# et312.net
KiCad netlist of a schematic drawn in EAGLE
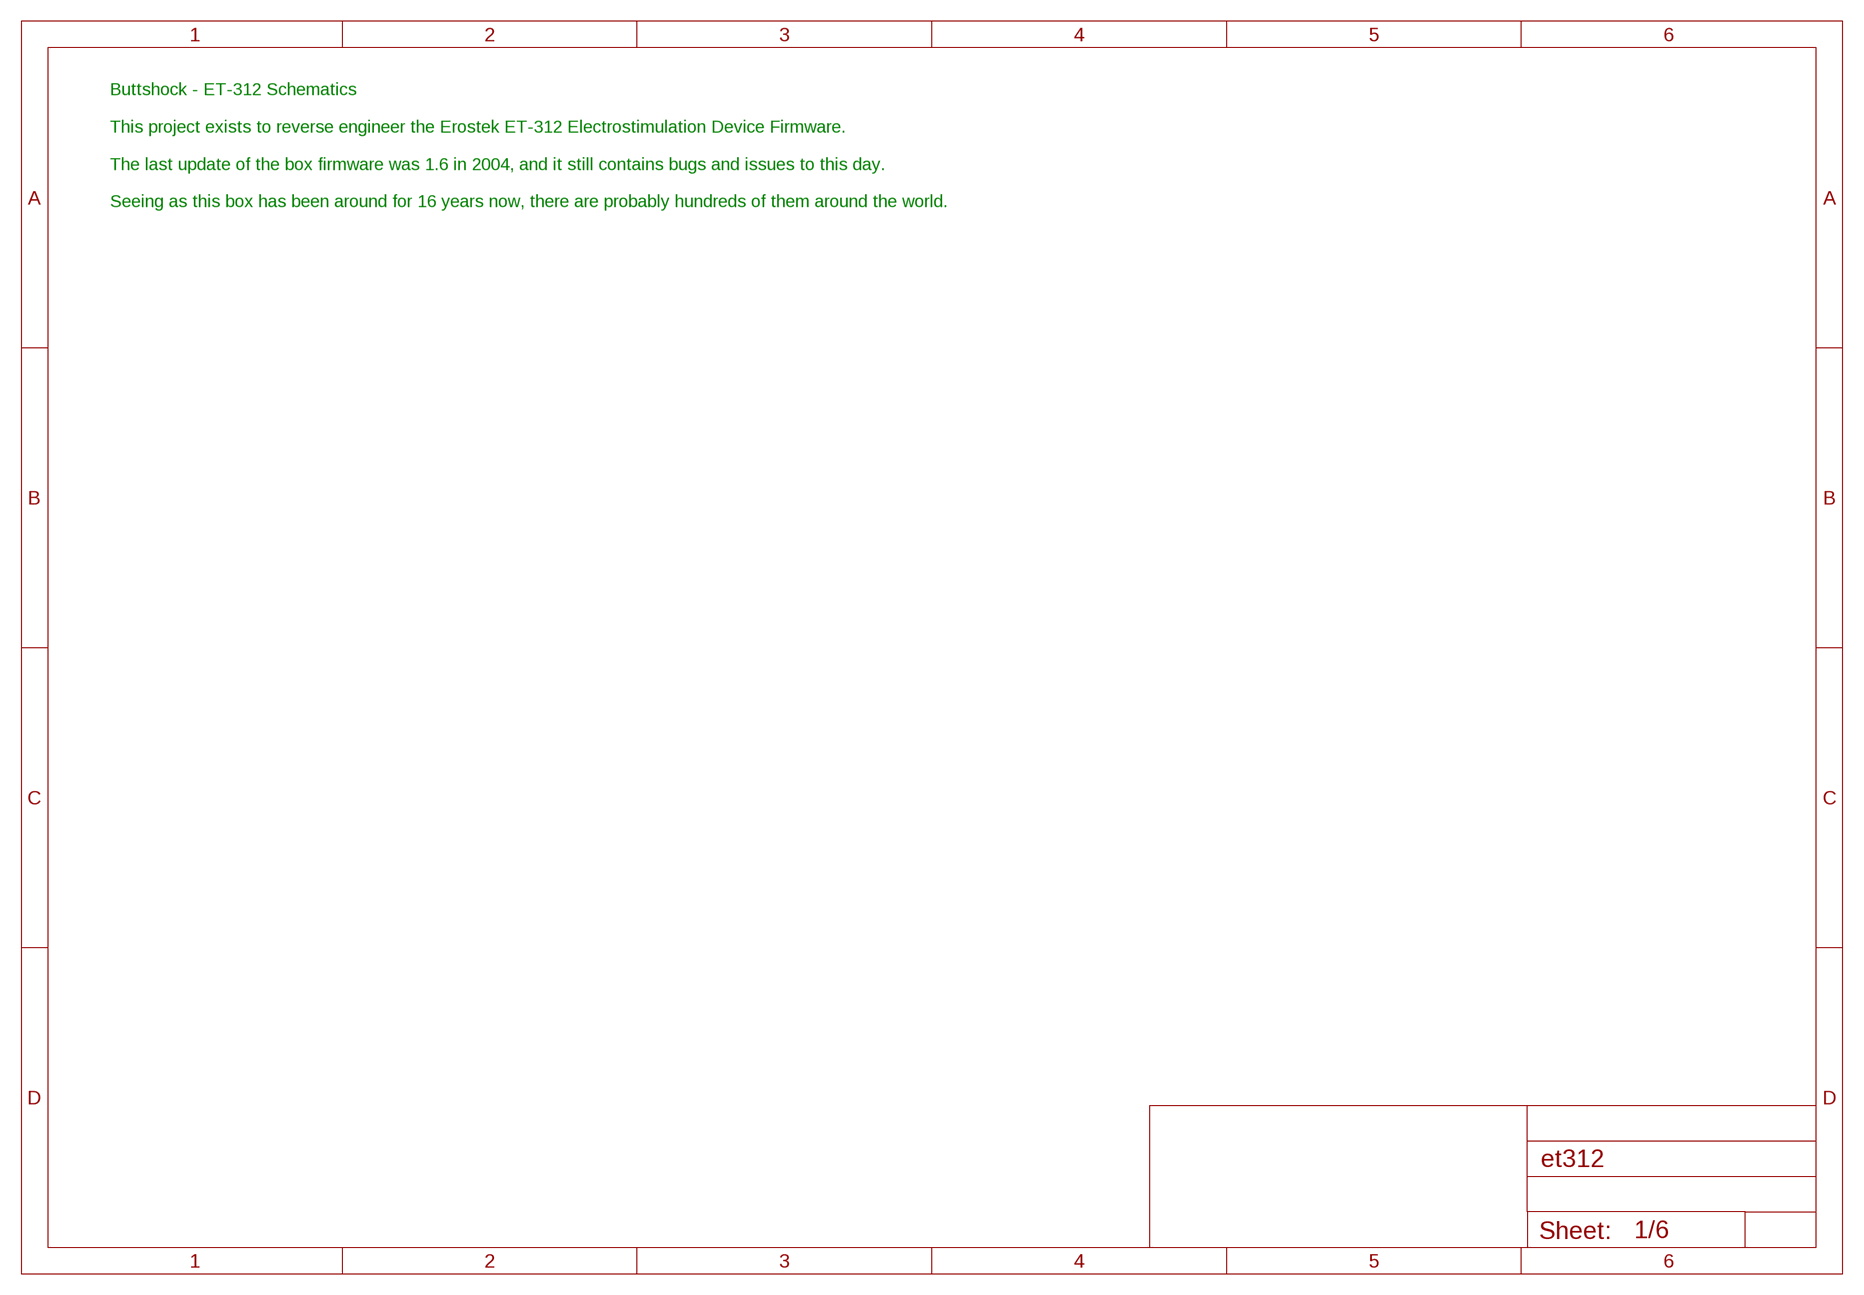
[diagram p0: schematic, sheet 1]
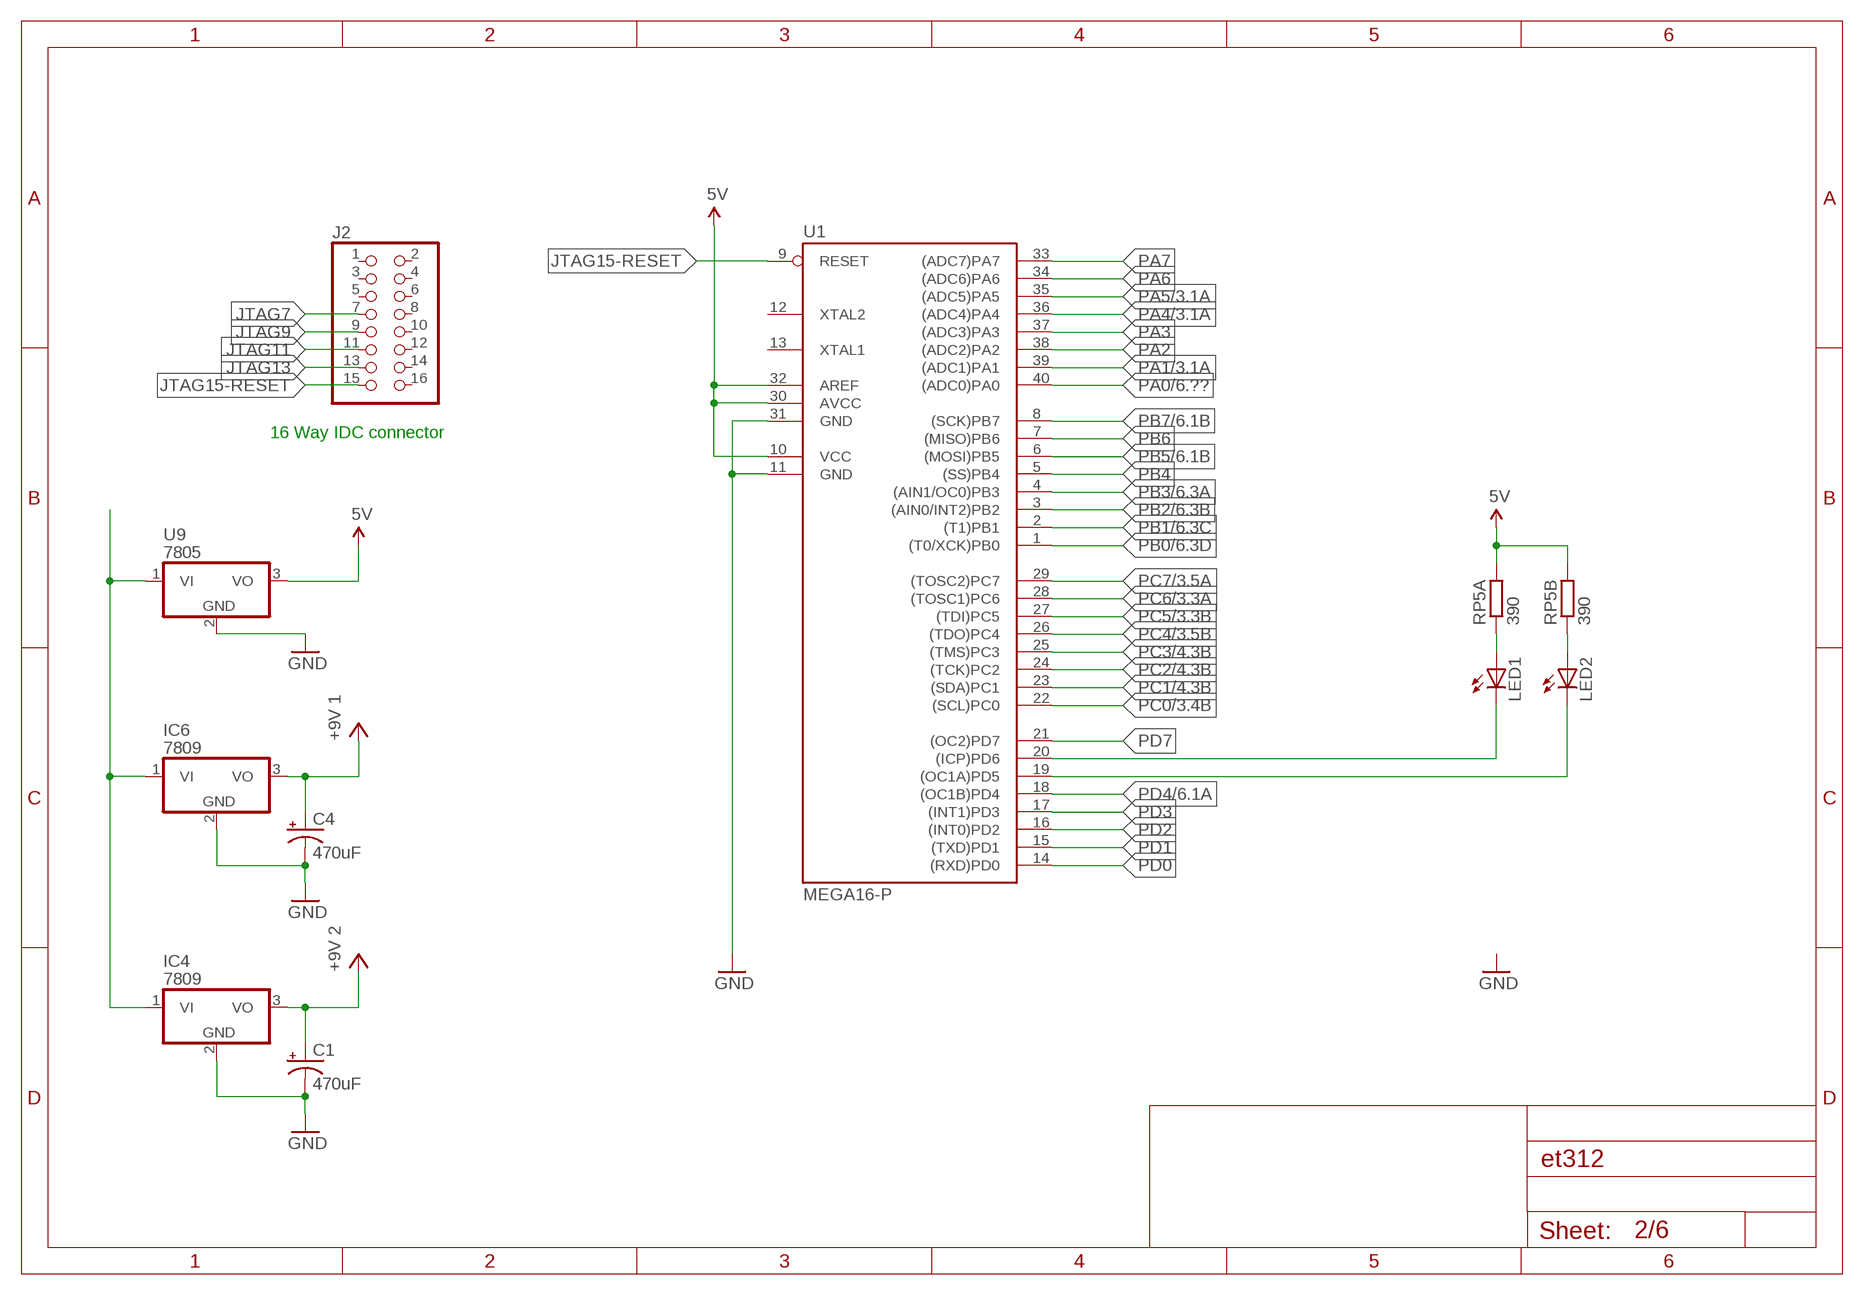
[diagram p1: schematic, sheet 2]
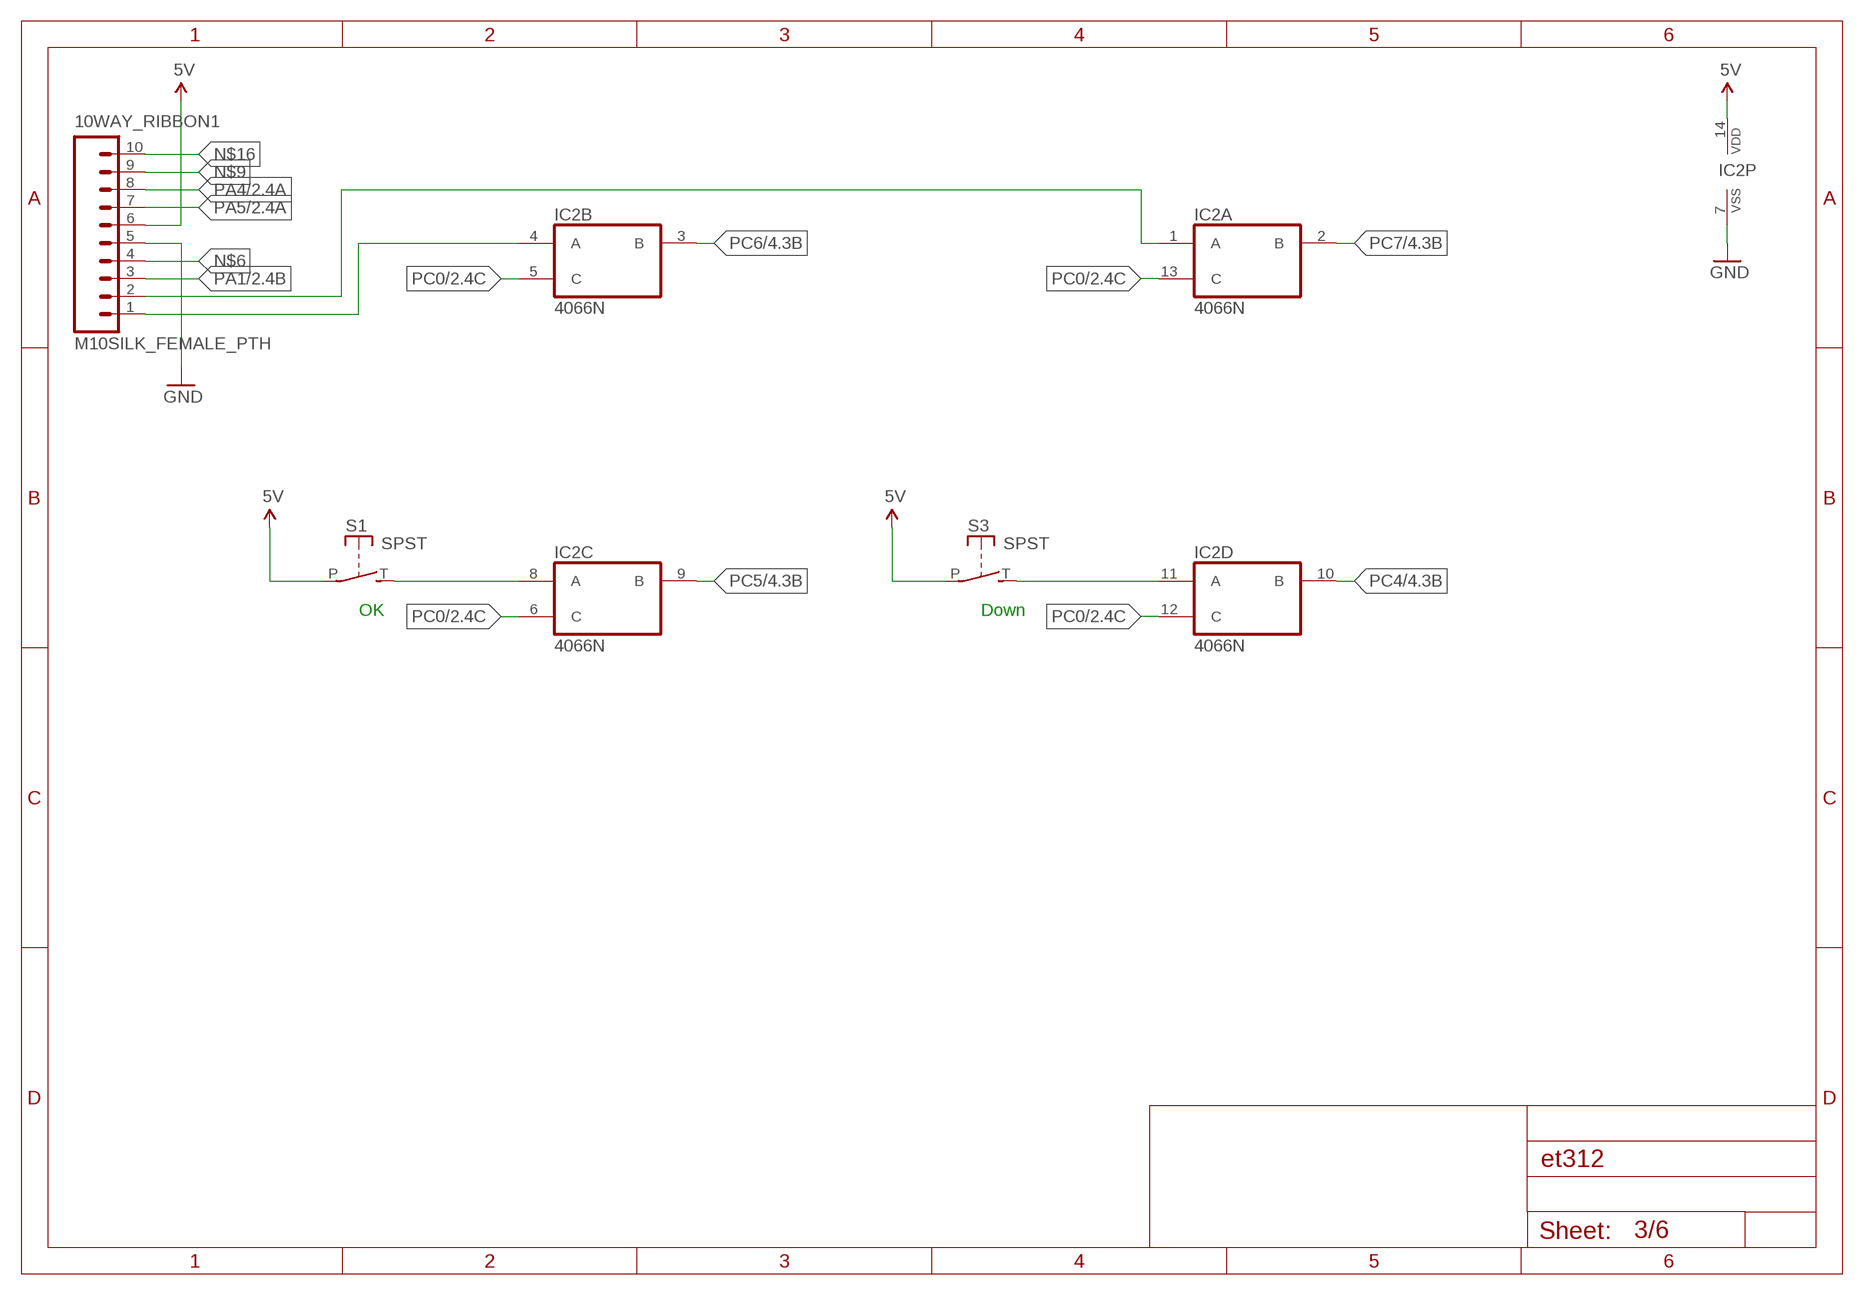
[diagram p2: schematic, sheet 3]
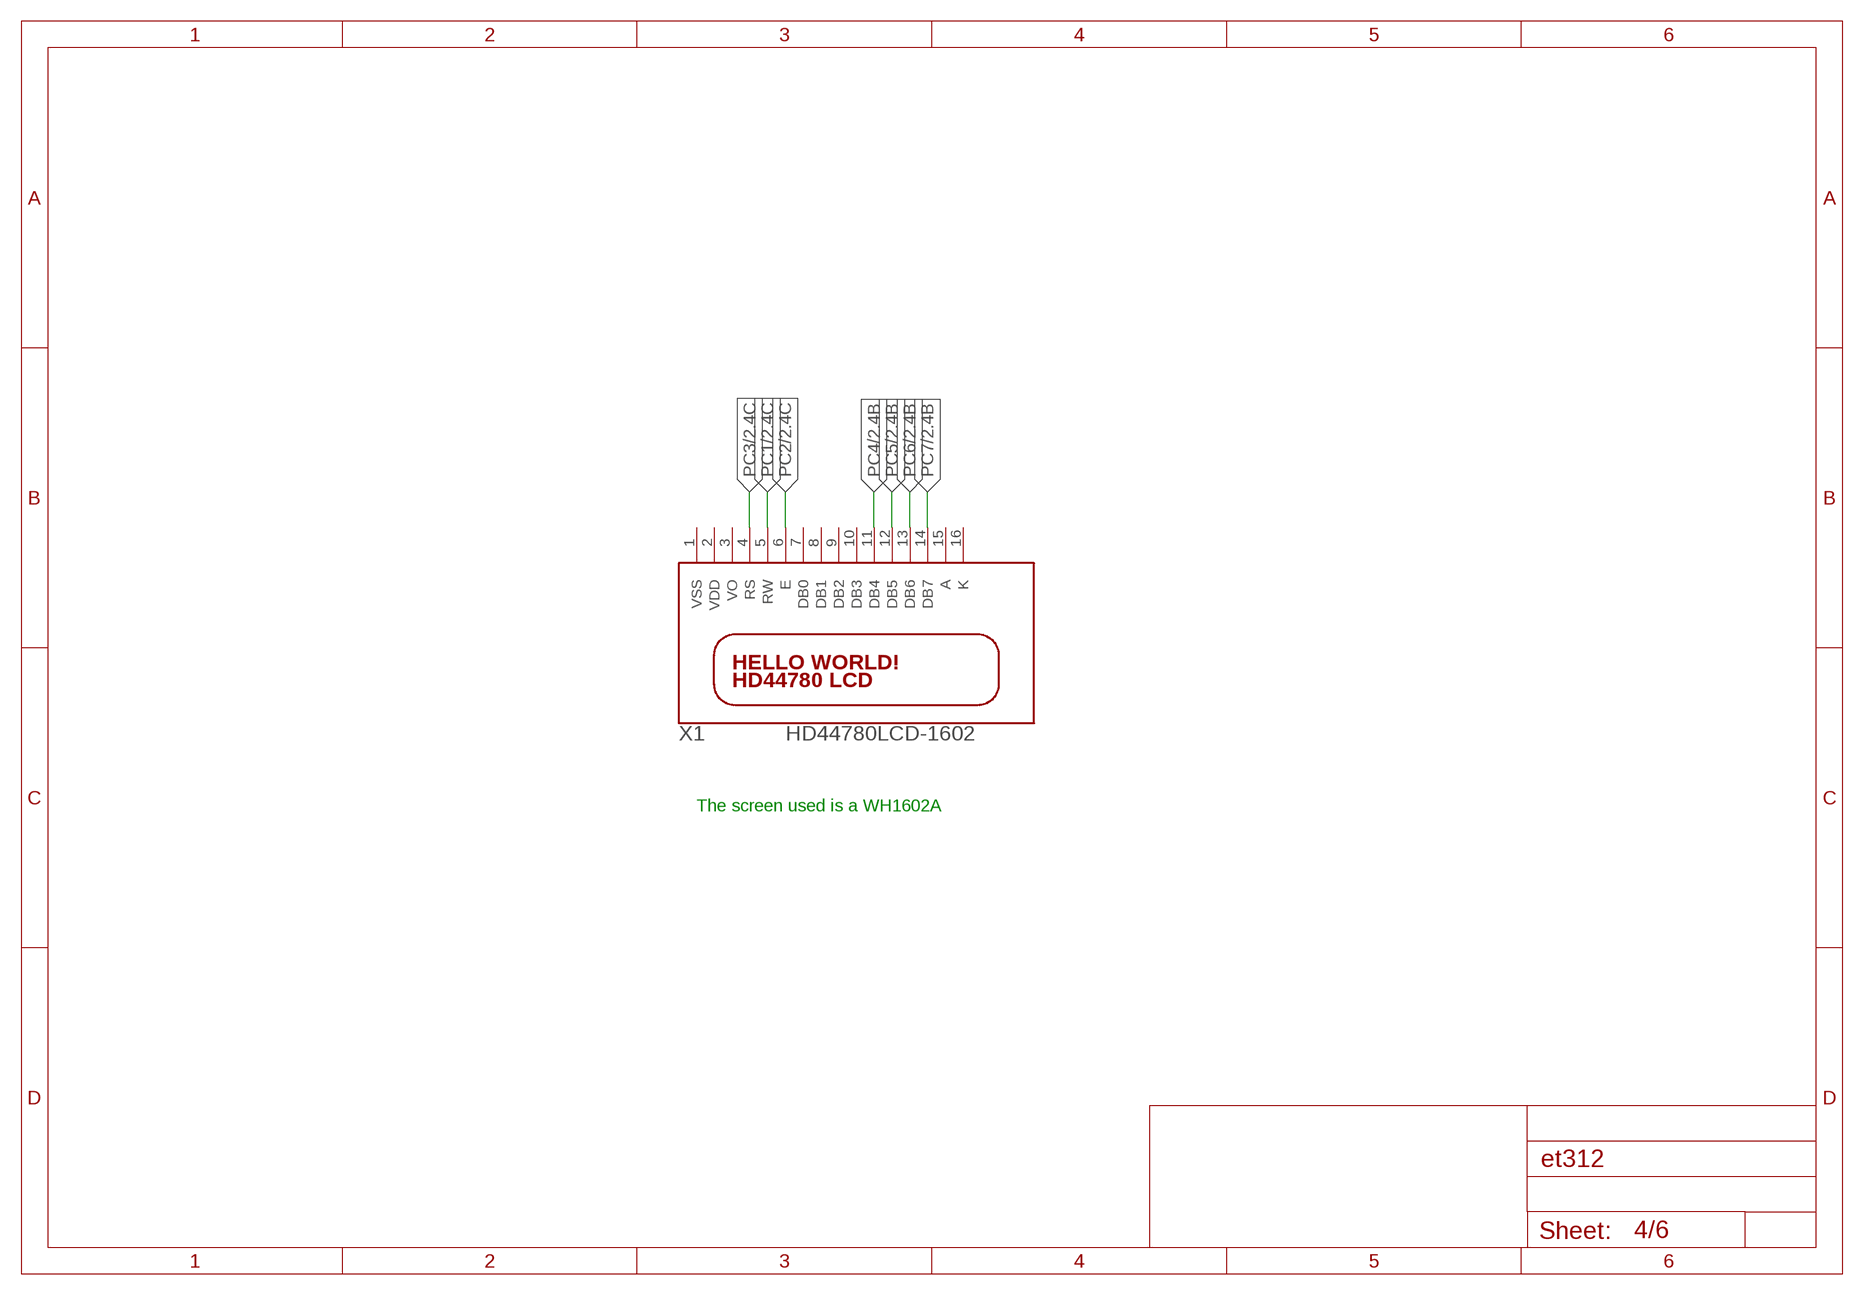
[diagram p3: schematic, sheet 4]
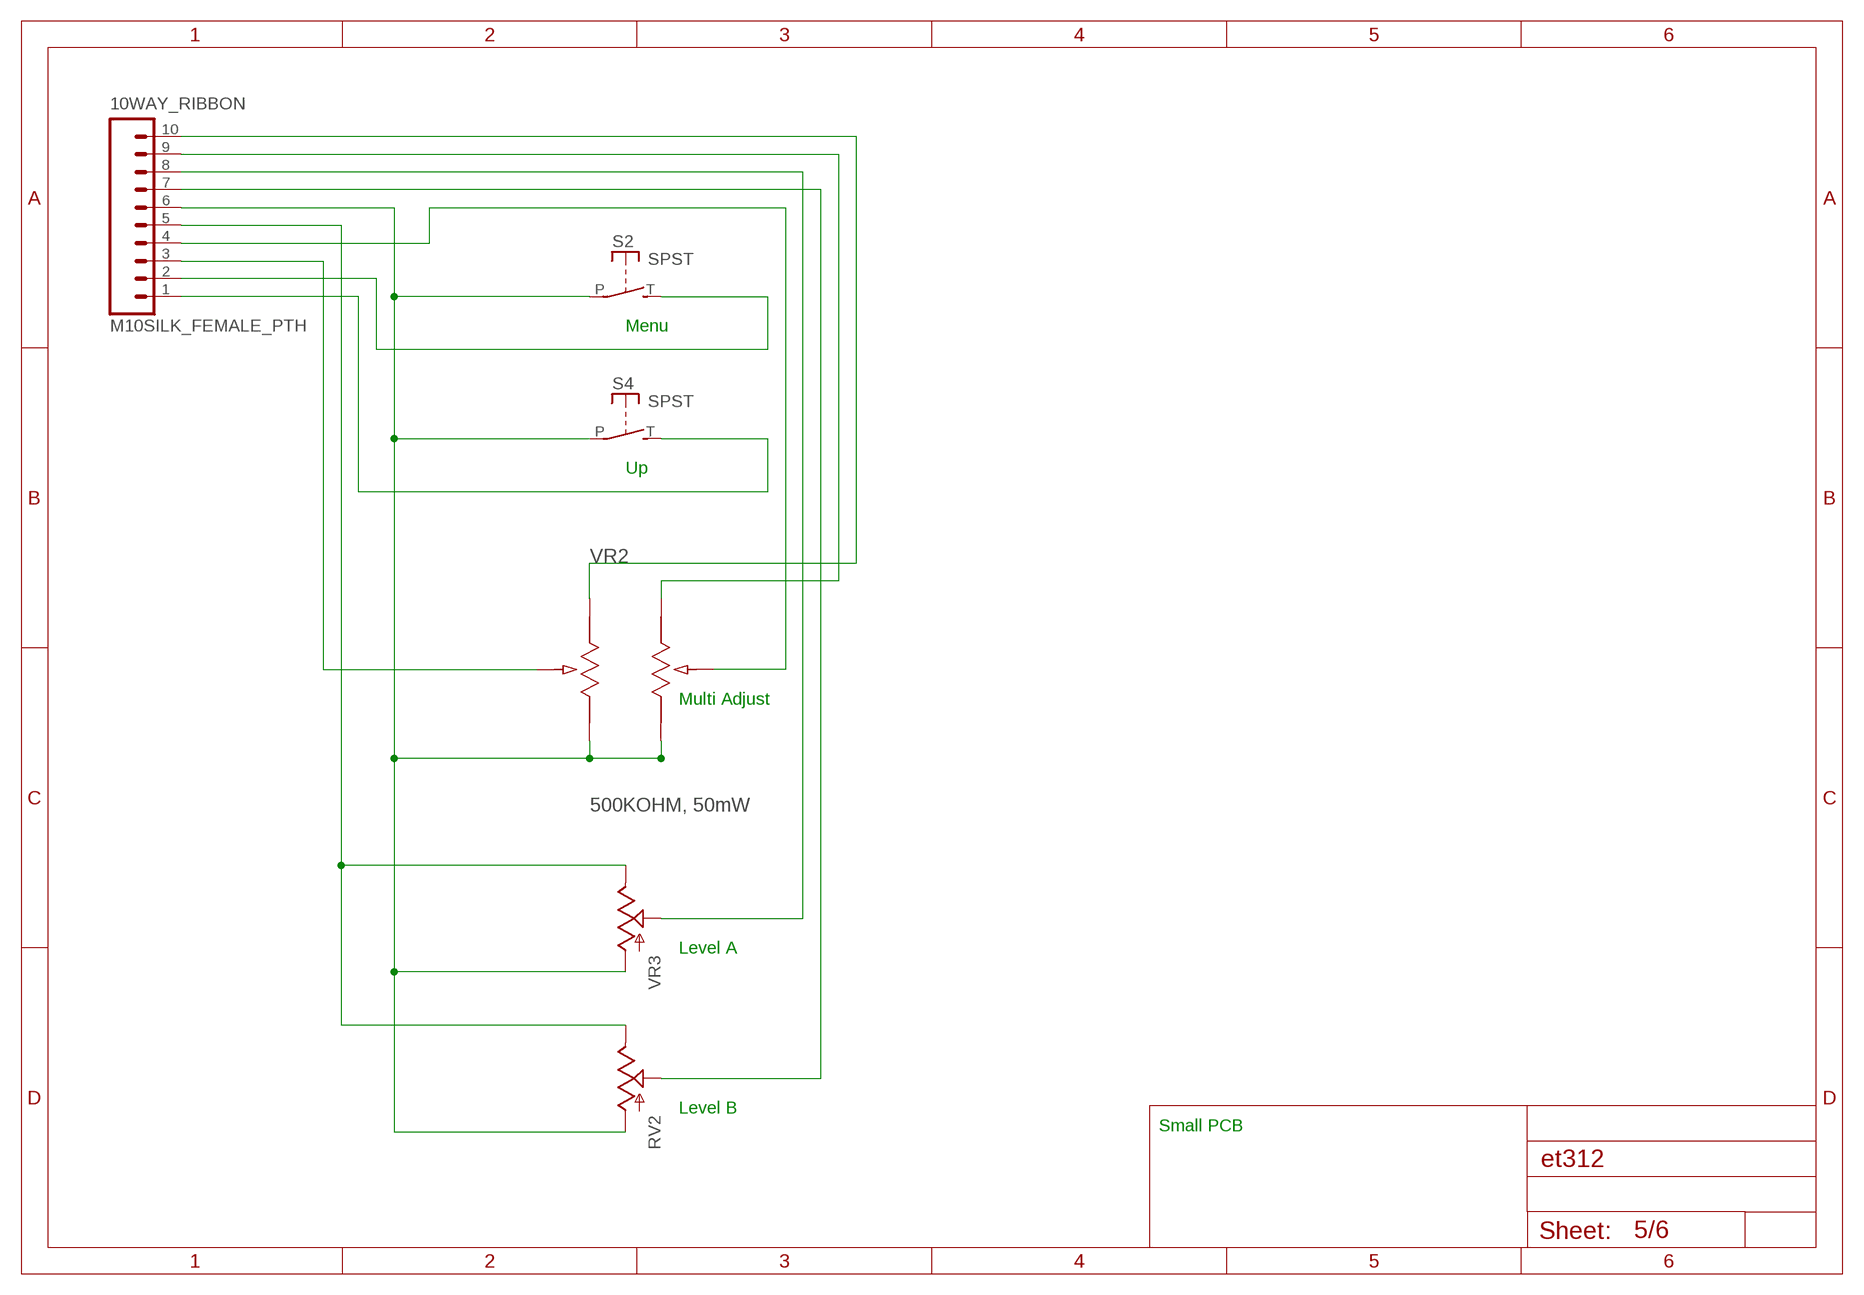
[diagram p4: schematic, sheet 5]
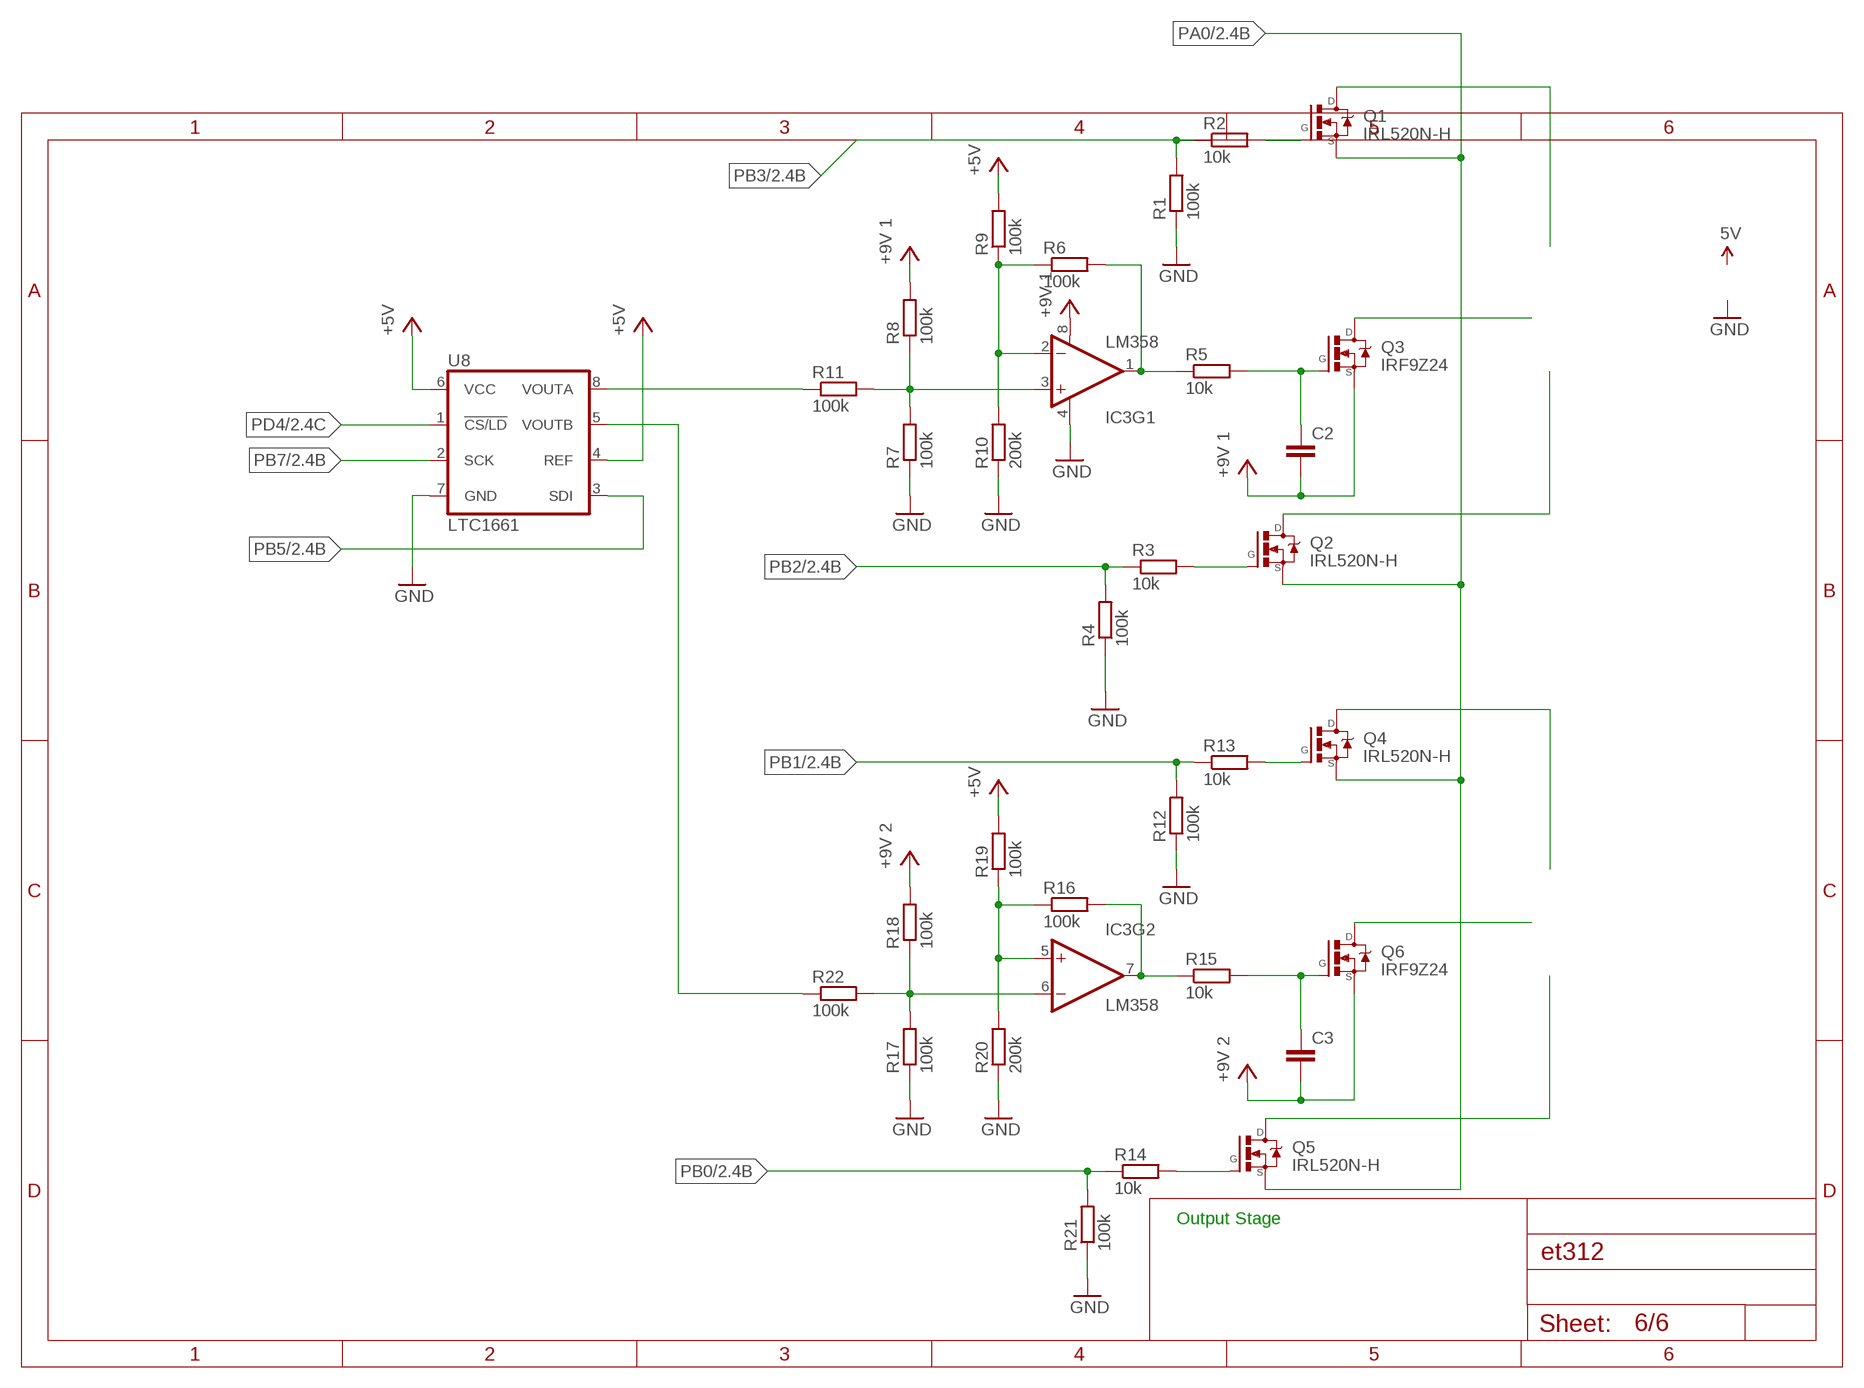
[diagram p5: schematic, sheet 6]

(export (version "E")
  (design (tool "Eeschema 10.0.6"))
  (components
    (comp (ref "10WAY_RIBBON1")
      (value "M10SILK_FEMALE_PTH")
      (footprint "eagle-import:1X10")
      (libsource (lib "eagle-import") (part "M10SILK_FEMALE_PTH"))
    )
    (comp (ref "IC2")
      (value "4066N")
      (footprint "eagle-import:DIL14")
      (libsource (lib "eagle-import") (part "4066N"))
    )
    (comp (ref "S1")
      (value "SPST")
      (footprint "eagle-import:JUDCOSPST")
      (libsource (lib "eagle-import") (part "SPST"))
    )
    (comp (ref "S3")
      (value "SPST")
      (footprint "eagle-import:JUDCOSPST")
      (libsource (lib "eagle-import") (part "SPST"))
    )
    (comp (ref "C2")
      (value "CAPPTH")
      (footprint "eagle-import:CAP-PTH-SMALL")
      (libsource (lib "eagle-import") (part "CAPPTH"))
    )
    (comp (ref "C3")
      (value "CAPPTH")
      (footprint "eagle-import:CAP-PTH-SMALL")
      (libsource (lib "eagle-import") (part "CAPPTH"))
    )
    (comp (ref "IC3")
      (value "LM358")
      (footprint "eagle-import:DIP08")
      (libsource (lib "eagle-import") (part "LM358"))
    )
    (comp (ref "Q1")
      (value "IRL520N-H")
      (footprint "eagle-import:TO220")
      (libsource (lib "eagle-import") (part "IRL530N-H"))
    )
    (comp (ref "Q2")
      (value "IRL520N-H")
      (footprint "eagle-import:TO220")
      (libsource (lib "eagle-import") (part "IRL530N-H"))
    )
    (comp (ref "Q3")
      (value "IRF9Z24")
      (footprint "eagle-import:TO220")
      (libsource (lib "eagle-import") (part "IRL530N-H"))
    )
    (comp (ref "Q4")
      (value "IRL520N-H")
      (footprint "eagle-import:TO220")
      (libsource (lib "eagle-import") (part "IRL530N-H"))
    )
    (comp (ref "Q5")
      (value "IRL520N-H")
      (footprint "eagle-import:TO220")
      (libsource (lib "eagle-import") (part "IRL530N-H"))
    )
    (comp (ref "Q6")
      (value "IRF9Z24")
      (footprint "eagle-import:TO220")
      (libsource (lib "eagle-import") (part "IRL530N-H"))
    )
    (comp (ref "R1")
      (value "100k")
      (footprint "eagle-import:0207_10")
      (libsource (lib "eagle-import") (part "R0207/10"))
    )
    (comp (ref "R2")
      (value "10k")
      (footprint "eagle-import:0207_10")
      (libsource (lib "eagle-import") (part "R0207/10"))
    )
    (comp (ref "R3")
      (value "10k")
      (footprint "eagle-import:0207_10")
      (libsource (lib "eagle-import") (part "R0207/10"))
    )
    (comp (ref "R4")
      (value "100k")
      (footprint "eagle-import:0207_10")
      (libsource (lib "eagle-import") (part "R0207/10"))
    )
    (comp (ref "R5")
      (value "10k")
      (footprint "eagle-import:0207_10")
      (libsource (lib "eagle-import") (part "R0207/10"))
    )
    (comp (ref "R6")
      (value "100k")
      (footprint "eagle-import:0207_10")
      (libsource (lib "eagle-import") (part "R0207/10"))
    )
    (comp (ref "R7")
      (value "100k")
      (footprint "eagle-import:0207_10")
      (libsource (lib "eagle-import") (part "R0207/10"))
    )
    (comp (ref "R8")
      (value "100k")
      (footprint "eagle-import:0207_10")
      (libsource (lib "eagle-import") (part "R0207/10"))
    )
    (comp (ref "R9")
      (value "100k")
      (footprint "eagle-import:0207_10")
      (libsource (lib "eagle-import") (part "R0207/10"))
    )
    (comp (ref "R10")
      (value "200k")
      (footprint "eagle-import:0207_10")
      (libsource (lib "eagle-import") (part "R0207/10"))
    )
    (comp (ref "R11")
      (value "100k")
      (footprint "eagle-import:0207_10")
      (libsource (lib "eagle-import") (part "R0207/10"))
    )
    (comp (ref "R12")
      (value "100k")
      (footprint "eagle-import:0207_10")
      (libsource (lib "eagle-import") (part "R0207/10"))
    )
    (comp (ref "R13")
      (value "10k")
      (footprint "eagle-import:0207_10")
      (libsource (lib "eagle-import") (part "R0207/10"))
    )
    (comp (ref "R14")
      (value "10k")
      (footprint "eagle-import:0207_10")
      (libsource (lib "eagle-import") (part "R0207/10"))
    )
    (comp (ref "R15")
      (value "10k")
      (footprint "eagle-import:0207_10")
      (libsource (lib "eagle-import") (part "R0207/10"))
    )
    (comp (ref "R16")
      (value "100k")
      (footprint "eagle-import:0207_10")
      (libsource (lib "eagle-import") (part "R0207/10"))
    )
    (comp (ref "R17")
      (value "100k")
      (footprint "eagle-import:0207_10")
      (libsource (lib "eagle-import") (part "R0207/10"))
    )
    (comp (ref "R18")
      (value "100k")
      (footprint "eagle-import:0207_10")
      (libsource (lib "eagle-import") (part "R0207/10"))
    )
    (comp (ref "R19")
      (value "100k")
      (footprint "eagle-import:0207_10")
      (libsource (lib "eagle-import") (part "R0207/10"))
    )
    (comp (ref "R20")
      (value "200k")
      (footprint "eagle-import:0207_10")
      (libsource (lib "eagle-import") (part "R0207/10"))
    )
    (comp (ref "R21")
      (value "100k")
      (footprint "eagle-import:0207_10")
      (libsource (lib "eagle-import") (part "R0207/10"))
    )
    (comp (ref "R22")
      (value "100k")
      (footprint "eagle-import:0207_10")
      (libsource (lib "eagle-import") (part "R0207/10"))
    )
    (comp (ref "U8")
      (value "LTC1661")
      (footprint "eagle-import:MSOP8")
      (fields (field (name "MPN") "LTC2602CMS8"))
      (libsource (lib "eagle-import") (part "LTC26MS802C"))
    )
    (comp (ref "X1")
      (value "HD44780LCD-1602")
      (footprint "eagle-import:LCD1602")
      (libsource (lib "eagle-import") (part "HD44780LCD-1602"))
    )
    (comp (ref "10WAY_RIBBON")
      (value "M10SILK_FEMALE_PTH")
      (footprint "eagle-import:1X10")
      (libsource (lib "eagle-import") (part "M10SILK_FEMALE_PTH"))
    )
    (comp (ref "RV2")
      (value "POT")
      (footprint "eagle-import:ALPS_POT")
      (libsource (lib "eagle-import") (part "POT"))
    )
    (comp (ref "S2")
      (value "SPST")
      (footprint "eagle-import:JUDCOSPST")
      (libsource (lib "eagle-import") (part "SPST"))
    )
    (comp (ref "S4")
      (value "SPST")
      (footprint "eagle-import:JUDCOSPST")
      (libsource (lib "eagle-import") (part "SPST"))
    )
    (comp (ref "VR2")
      (value "500KOHM, 50mW")
      (footprint "eagle-import:POT_EVJC20")
      (fields (field (name "MPN") "EVJC20F02A14"))
      (libsource (lib "eagle-import") (part "EVJ-JC2C20F02A14"))
    )
    (comp (ref "VR3")
      (value "POT")
      (footprint "eagle-import:ALPS_POT")
      (libsource (lib "eagle-import") (part "POT"))
    )
    (comp (ref "C1")
      (value "470uF")
      (footprint "eagle-import:CPOL-RADIAL-100UF-25V")
      (libsource (lib "eagle-import") (part "CAP_POLPTH1"))
    )
    (comp (ref "C4")
      (value "470uF")
      (footprint "eagle-import:CPOL-RADIAL-100UF-25V")
      (libsource (lib "eagle-import") (part "CAP_POLPTH1"))
    )
    (comp (ref "IC4")
      (value "7809")
      (footprint "eagle-import:TO220H")
      (libsource (lib "eagle-import") (part "78T05"))
    )
    (comp (ref "IC6")
      (value "7809")
      (footprint "eagle-import:TO220H")
      (libsource (lib "eagle-import") (part "78T05"))
    )
    (comp (ref "J2")
      (value "PINHD-2X8")
      (footprint "eagle-import:2X08")
      (libsource (lib "eagle-import") (part "PINHD-2X8"))
    )
    (comp (ref "LED1")
      (value "LED3MM")
      (footprint "eagle-import:LED3MM")
      (libsource (lib "eagle-import") (part "LED3MM"))
    )
    (comp (ref "LED2")
      (value "LED3MM")
      (footprint "eagle-import:LED3MM")
      (libsource (lib "eagle-import") (part "LED3MM"))
    )
    (comp (ref "RP5A")
      (value "390")
      (footprint "eagle-import:0207_7")
      (libsource (lib "eagle-import") (part "R-EU_0207/7"))
    )
    (comp (ref "RP5B")
      (value "390")
      (footprint "eagle-import:0207_7")
      (libsource (lib "eagle-import") (part "R-EU_0207/7"))
    )
    (comp (ref "U1")
      (value "MEGA16-P")
      (footprint "eagle-import:DIL40")
      (fields (field (name "MPN") "ATMEGA16-16PU"))
      (libsource (lib "eagle-import") (part "MEGA16-P"))
    )
    (comp (ref "U9")
      (value "7805")
      (footprint "eagle-import:TO220H")
      (libsource (lib "eagle-import") (part "78T05"))
    )
  )
  (nets
    (net (code "1") (name "5V") (class "Default")
      (node (ref "10WAY_RIBBON1") (pin "6") (pinfunction "6_6") (pintype "passive"))
      (node (ref "IC2") (pin "14") (pinfunction "VDD_14") (pintype "power_in"))
      (node (ref "RP5A") (pin "2") (pinfunction "2_2") (pintype "passive"))
      (node (ref "RP5B") (pin "2") (pinfunction "2_2") (pintype "passive"))
      (node (ref "S1") (pin "P") (pinfunction "P_P") (pintype "passive"))
      (node (ref "S3") (pin "P") (pinfunction "P_P") (pintype "passive"))
      (node (ref "U1") (pin "10") (pinfunction "VCC_10") (pintype "power_in"))
      (node (ref "U1") (pin "30") (pinfunction "AVCC_30") (pintype "power_in"))
      (node (ref "U1") (pin "32") (pinfunction "AREF_32") (pintype "passive"))
      (node (ref "U9") (pin "3") (pinfunction "VO_3") (pintype "passive"))
    )
    (net (code "2") (name "GND") (class "Default")
      (node (ref "10WAY_RIBBON1") (pin "5") (pinfunction "5_5") (pintype "passive"))
      (node (ref "C1") (pin "2") (pinfunction "-_2") (pintype "passive"))
      (node (ref "C4") (pin "2") (pinfunction "-_2") (pintype "passive"))
      (node (ref "IC2") (pin "7") (pinfunction "VSS_7") (pintype "power_in"))
      (node (ref "IC3") (pin "4") (pinfunction "V-_4") (pintype "power_in"))
      (node (ref "IC4") (pin "2") (pinfunction "GND_2") (pintype "passive"))
      (node (ref "IC6") (pin "2") (pinfunction "GND_2") (pintype "passive"))
      (node (ref "R1") (pin "1") (pinfunction "1_1") (pintype "passive"))
      (node (ref "R10") (pin "1") (pinfunction "1_1") (pintype "passive"))
      (node (ref "R12") (pin "1") (pinfunction "1_1") (pintype "passive"))
      (node (ref "R17") (pin "1") (pinfunction "1_1") (pintype "passive"))
      (node (ref "R20") (pin "1") (pinfunction "1_1") (pintype "passive"))
      (node (ref "R21") (pin "1") (pinfunction "1_1") (pintype "passive"))
      (node (ref "R4") (pin "1") (pinfunction "1_1") (pintype "passive"))
      (node (ref "R7") (pin "1") (pinfunction "1_1") (pintype "passive"))
      (node (ref "U1") (pin "11") (pinfunction "GND_11") (pintype "power_in"))
      (node (ref "U1") (pin "31") (pinfunction "GND_31") (pintype "power_in"))
      (node (ref "U8") (pin "7") (pinfunction "GND_7") (pintype "power_in"))
      (node (ref "U9") (pin "2") (pinfunction "GND_2") (pintype "passive"))
    )
    (net (code "3") (name "JTAG7") (class "Default")
      (node (ref "J2") (pin "7") (pinfunction "7_7") (pintype "passive"))
    )
    (net (code "4") (name "JTAG9") (class "Default")
      (node (ref "J2") (pin "9") (pinfunction "9_9") (pintype "passive"))
    )
    (net (code "5") (name "JTAG11") (class "Default")
      (node (ref "J2") (pin "11") (pinfunction "11_11") (pintype "passive"))
    )
    (net (code "6") (name "JTAG13") (class "Default")
      (node (ref "J2") (pin "13") (pinfunction "13_13") (pintype "passive"))
    )
    (net (code "7") (name "JTAG15-RESET") (class "Default")
      (node (ref "J2") (pin "15") (pinfunction "15_15") (pintype "passive"))
      (node (ref "U1") (pin "9") (pinfunction "RESET_9") (pintype "input"))
    )
    (net (code "8") (name "N$6") (class "Default")
      (node (ref "10WAY_RIBBON1") (pin "4") (pinfunction "4_4") (pintype "passive"))
    )
    (net (code "9") (name "N$9") (class "Default")
      (node (ref "10WAY_RIBBON1") (pin "9") (pinfunction "9_9") (pintype "passive"))
    )
    (net (code "10") (name "N$16") (class "Default")
      (node (ref "10WAY_RIBBON1") (pin "10") (pinfunction "10_10") (pintype "passive"))
    )
    (net (code "11") (name "Net-(10WAY_RIBBON-Pad3)") (class "Default")
      (node (ref "10WAY_RIBBON") (pin "3") (pinfunction "3_3") (pintype "passive"))
      (node (ref "VR2") (pin "2") (pinfunction "2_2") (pintype "passive"))
    )
    (net (code "12") (name "Net-(10WAY_RIBBON-Pad4)") (class "Default")
      (node (ref "10WAY_RIBBON") (pin "4") (pinfunction "4_4") (pintype "passive"))
      (node (ref "VR2") (pin "2'") (pinfunction "2'_2'") (pintype "passive"))
    )
    (net (code "13") (name "Net-(10WAY_RIBBON-Pad9)") (class "Default")
      (node (ref "10WAY_RIBBON") (pin "9") (pinfunction "9_9") (pintype "passive"))
      (node (ref "VR2") (pin "3'") (pinfunction "3'_3'") (pintype "passive"))
    )
    (net (code "14") (name "Net-(10WAY_RIBBON-Pad10)") (class "Default")
      (node (ref "10WAY_RIBBON") (pin "10") (pinfunction "10_10") (pintype "passive"))
      (node (ref "VR2") (pin "3") (pinfunction "3_3") (pintype "passive"))
    )
    (net (code "15") (name "Net-(IC2A-A)") (class "Default")
      (node (ref "10WAY_RIBBON1") (pin "2") (pinfunction "2_2") (pintype "passive"))
      (node (ref "IC2") (pin "1") (pinfunction "A_1") (pintype "tri_state"))
    )
    (net (code "16") (name "Net-(IC2B-A)") (class "Default")
      (node (ref "10WAY_RIBBON1") (pin "1") (pinfunction "1_1") (pintype "passive"))
      (node (ref "IC2") (pin "4") (pinfunction "A_4") (pintype "tri_state"))
    )
    (net (code "17") (name "Net-(IC2C-A)") (class "Default")
      (node (ref "IC2") (pin "8") (pinfunction "A_8") (pintype "tri_state"))
      (node (ref "S1") (pin "T") (pinfunction "S_T") (pintype "passive"))
    )
    (net (code "18") (name "Net-(IC2D-A)") (class "Default")
      (node (ref "IC2") (pin "11") (pinfunction "A_11") (pintype "tri_state"))
      (node (ref "S3") (pin "T") (pinfunction "S_T") (pintype "passive"))
    )
    (net (code "19") (name "Net-(IC3A-+IN)") (class "Default")
      (node (ref "IC3") (pin "3") (pinfunction "+IN_3") (pintype "input"))
      (node (ref "R11") (pin "2") (pinfunction "2_2") (pintype "passive"))
      (node (ref "R7") (pin "2") (pinfunction "2_2") (pintype "passive"))
      (node (ref "R8") (pin "1") (pinfunction "1_1") (pintype "passive"))
    )
    (net (code "20") (name "Net-(IC3A--IN)") (class "Default")
      (node (ref "IC3") (pin "2") (pinfunction "-IN_2") (pintype "input"))
      (node (ref "R10") (pin "2") (pinfunction "2_2") (pintype "passive"))
      (node (ref "R6") (pin "1") (pinfunction "1_1") (pintype "passive"))
      (node (ref "R9") (pin "1") (pinfunction "1_1") (pintype "passive"))
    )
    (net (code "21") (name "Net-(IC3A-OUT)") (class "Default")
      (node (ref "IC3") (pin "1") (pinfunction "OUT_1") (pintype "output"))
      (node (ref "R5") (pin "1") (pinfunction "1_1") (pintype "passive"))
      (node (ref "R6") (pin "2") (pinfunction "2_2") (pintype "passive"))
    )
    (net (code "22") (name "Net-(IC3B-+IN)") (class "Default")
      (node (ref "IC3") (pin "5") (pinfunction "+IN_5") (pintype "input"))
      (node (ref "R16") (pin "1") (pinfunction "1_1") (pintype "passive"))
      (node (ref "R19") (pin "1") (pinfunction "1_1") (pintype "passive"))
      (node (ref "R20") (pin "2") (pinfunction "2_2") (pintype "passive"))
    )
    (net (code "23") (name "Net-(IC3B--IN)") (class "Default")
      (node (ref "IC3") (pin "6") (pinfunction "-IN_6") (pintype "input"))
      (node (ref "R17") (pin "2") (pinfunction "2_2") (pintype "passive"))
      (node (ref "R18") (pin "1") (pinfunction "1_1") (pintype "passive"))
      (node (ref "R22") (pin "2") (pinfunction "2_2") (pintype "passive"))
    )
    (net (code "24") (name "Net-(IC3B-OUT)") (class "Default")
      (node (ref "IC3") (pin "7") (pinfunction "OUT_7") (pintype "output"))
      (node (ref "R15") (pin "1") (pinfunction "1_1") (pintype "passive"))
      (node (ref "R16") (pin "2") (pinfunction "2_2") (pintype "passive"))
    )
    (net (code "25") (name "Net-(IC4-VI)") (class "Default")
      (node (ref "IC4") (pin "1") (pinfunction "VI_1") (pintype "input"))
      (node (ref "IC6") (pin "1") (pinfunction "VI_1") (pintype "input"))
      (node (ref "U9") (pin "1") (pinfunction "VI_1") (pintype "input"))
    )
    (net (code "26") (name "Net-(LED1-C)") (class "Default")
      (node (ref "LED1") (pin "K") (pinfunction "C_K") (pintype "passive"))
      (node (ref "U1") (pin "20") (pinfunction "(ICP)PD6_20") (pintype "bidirectional"))
    )
    (net (code "27") (name "Net-(LED1-PadA)") (class "Default")
      (node (ref "LED1") (pin "A") (pinfunction "A_A") (pintype "passive"))
      (node (ref "RP5A") (pin "1") (pinfunction "1_1") (pintype "passive"))
    )
    (net (code "28") (name "Net-(LED2-C)") (class "Default")
      (node (ref "LED2") (pin "K") (pinfunction "C_K") (pintype "passive"))
      (node (ref "U1") (pin "19") (pinfunction "(OC1A)PD5_19") (pintype "bidirectional"))
    )
    (net (code "29") (name "Net-(LED2-PadA)") (class "Default")
      (node (ref "LED2") (pin "A") (pinfunction "A_A") (pintype "passive"))
      (node (ref "RP5B") (pin "1") (pinfunction "1_1") (pintype "passive"))
    )
    (net (code "30") (name "Net-(Q1-G)") (class "Default")
      (node (ref "Q1") (pin "1") (pinfunction "G_1") (pintype "passive"))
      (node (ref "R2") (pin "2") (pinfunction "2_2") (pintype "passive"))
    )
    (net (code "31") (name "Net-(Q2-G)") (class "Default")
      (node (ref "Q2") (pin "1") (pinfunction "G_1") (pintype "passive"))
      (node (ref "R3") (pin "2") (pinfunction "2_2") (pintype "passive"))
    )
    (net (code "32") (name "Net-(Q3-G)") (class "Default")
      (node (ref "C2") (pin "1") (pinfunction "1_1") (pintype "passive"))
      (node (ref "Q3") (pin "1") (pinfunction "G_1") (pintype "passive"))
      (node (ref "R5") (pin "2") (pinfunction "2_2") (pintype "passive"))
    )
    (net (code "33") (name "Net-(Q4-G)") (class "Default")
      (node (ref "Q4") (pin "1") (pinfunction "G_1") (pintype "passive"))
      (node (ref "R13") (pin "2") (pinfunction "2_2") (pintype "passive"))
    )
    (net (code "34") (name "Net-(Q5-G)") (class "Default")
      (node (ref "Q5") (pin "1") (pinfunction "G_1") (pintype "passive"))
      (node (ref "R14") (pin "2") (pinfunction "2_2") (pintype "passive"))
    )
    (net (code "35") (name "Net-(Q6-G)") (class "Default")
      (node (ref "C3") (pin "1") (pinfunction "1_1") (pintype "passive"))
      (node (ref "Q6") (pin "1") (pinfunction "G_1") (pintype "passive"))
      (node (ref "R15") (pin "2") (pinfunction "2_2") (pintype "passive"))
    )
    (net (code "36") (name "Net-(RV2-A)") (class "Default")
      (node (ref "10WAY_RIBBON") (pin "6") (pinfunction "6_6") (pintype "passive"))
      (node (ref "RV2") (pin "P$3") (pinfunction "A_P$3") (pintype "passive"))
      (node (ref "S2") (pin "P") (pinfunction "P_P") (pintype "passive"))
      (node (ref "S4") (pin "P") (pinfunction "P_P") (pintype "passive"))
      (node (ref "VR2") (pin "1") (pinfunction "1_1") (pintype "passive"))
      (node (ref "VR2") (pin "1'") (pinfunction "1'_1'") (pintype "passive"))
      (node (ref "VR3") (pin "P$3") (pinfunction "A_P$3") (pintype "passive"))
    )
    (net (code "37") (name "Net-(RV2-E)") (class "Default")
      (node (ref "10WAY_RIBBON") (pin "5") (pinfunction "5_5") (pintype "passive"))
      (node (ref "RV2") (pin "P$1") (pinfunction "E_P$1") (pintype "passive"))
      (node (ref "VR3") (pin "P$1") (pinfunction "E_P$1") (pintype "passive"))
    )
    (net (code "38") (name "Net-(RV2-S)") (class "Default")
      (node (ref "10WAY_RIBBON") (pin "7") (pinfunction "7_7") (pintype "passive"))
      (node (ref "RV2") (pin "P$2") (pinfunction "S_P$2") (pintype "passive"))
    )
    (net (code "39") (name "Net-(S2-S)") (class "Default")
      (node (ref "10WAY_RIBBON") (pin "2") (pinfunction "2_2") (pintype "passive"))
      (node (ref "S2") (pin "T") (pinfunction "S_T") (pintype "passive"))
    )
    (net (code "40") (name "Net-(S4-S)") (class "Default")
      (node (ref "10WAY_RIBBON") (pin "1") (pinfunction "1_1") (pintype "passive"))
      (node (ref "S4") (pin "T") (pinfunction "S_T") (pintype "passive"))
    )
    (net (code "41") (name "Net-(U8-VOUTA)") (class "Default")
      (node (ref "R11") (pin "1") (pinfunction "1_1") (pintype "passive"))
      (node (ref "U8") (pin "8") (pinfunction "VOUTA_8") (pintype "output"))
    )
    (net (code "42") (name "Net-(U8-VOUTB)") (class "Default")
      (node (ref "R22") (pin "1") (pinfunction "1_1") (pintype "passive"))
      (node (ref "U8") (pin "5") (pinfunction "VOUTB_5") (pintype "output"))
    )
    (net (code "43") (name "Net-(VR3-S)") (class "Default")
      (node (ref "10WAY_RIBBON") (pin "8") (pinfunction "8_8") (pintype "passive"))
      (node (ref "VR3") (pin "P$2") (pinfunction "S_P$2") (pintype "passive"))
    )
    (net (code "44") (name "PA0") (class "Default")
      (node (ref "Q1") (pin "3") (pinfunction "S_3") (pintype "passive"))
      (node (ref "Q2") (pin "3") (pinfunction "S_3") (pintype "passive"))
      (node (ref "Q4") (pin "3") (pinfunction "S_3") (pintype "passive"))
      (node (ref "Q5") (pin "3") (pinfunction "S_3") (pintype "passive"))
      (node (ref "U1") (pin "40") (pinfunction "(ADC0)PA0_40") (pintype "bidirectional"))
    )
    (net (code "45") (name "PA1") (class "Default")
      (node (ref "10WAY_RIBBON1") (pin "3") (pinfunction "3_3") (pintype "passive"))
      (node (ref "U1") (pin "39") (pinfunction "(ADC1)PA1_39") (pintype "bidirectional"))
    )
    (net (code "46") (name "PA2") (class "Default")
      (node (ref "U1") (pin "38") (pinfunction "(ADC2)PA2_38") (pintype "bidirectional"))
    )
    (net (code "47") (name "PA3") (class "Default")
      (node (ref "U1") (pin "37") (pinfunction "(ADC3)PA3_37") (pintype "bidirectional"))
    )
    (net (code "48") (name "PA4") (class "Default")
      (node (ref "10WAY_RIBBON1") (pin "8") (pinfunction "8_8") (pintype "passive"))
      (node (ref "U1") (pin "36") (pinfunction "(ADC4)PA4_36") (pintype "bidirectional"))
    )
    (net (code "49") (name "PA5") (class "Default")
      (node (ref "10WAY_RIBBON1") (pin "7") (pinfunction "7_7") (pintype "passive"))
      (node (ref "U1") (pin "35") (pinfunction "(ADC5)PA5_35") (pintype "bidirectional"))
    )
    (net (code "50") (name "PA6") (class "Default")
      (node (ref "U1") (pin "34") (pinfunction "(ADC6)PA6_34") (pintype "bidirectional"))
    )
    (net (code "51") (name "PA7") (class "Default")
      (node (ref "U1") (pin "33") (pinfunction "(ADC7)PA7_33") (pintype "bidirectional"))
    )
    (net (code "52") (name "PB0") (class "Default")
      (node (ref "R14") (pin "1") (pinfunction "1_1") (pintype "passive"))
      (node (ref "R21") (pin "2") (pinfunction "2_2") (pintype "passive"))
      (node (ref "U1") (pin "1") (pinfunction "(T0/XCK)PB0_1") (pintype "bidirectional"))
    )
    (net (code "53") (name "PB1") (class "Default")
      (node (ref "R12") (pin "2") (pinfunction "2_2") (pintype "passive"))
      (node (ref "R13") (pin "1") (pinfunction "1_1") (pintype "passive"))
      (node (ref "U1") (pin "2") (pinfunction "(T1)PB1_2") (pintype "bidirectional"))
    )
    (net (code "54") (name "PB2") (class "Default")
      (node (ref "R3") (pin "1") (pinfunction "1_1") (pintype "passive"))
      (node (ref "R4") (pin "2") (pinfunction "2_2") (pintype "passive"))
      (node (ref "U1") (pin "3") (pinfunction "(AIN0/INT2)PB2_3") (pintype "bidirectional"))
    )
    (net (code "55") (name "PB3") (class "Default")
      (node (ref "R1") (pin "2") (pinfunction "2_2") (pintype "passive"))
      (node (ref "R2") (pin "1") (pinfunction "1_1") (pintype "passive"))
      (node (ref "U1") (pin "4") (pinfunction "(AIN1/OC0)PB3_4") (pintype "bidirectional"))
    )
    (net (code "56") (name "PB4") (class "Default")
      (node (ref "U1") (pin "5") (pinfunction "(SS)PB4_5") (pintype "bidirectional"))
    )
    (net (code "57") (name "PB5") (class "Default")
      (node (ref "U1") (pin "6") (pinfunction "(MOSI)PB5_6") (pintype "bidirectional"))
      (node (ref "U8") (pin "3") (pinfunction "SDI_3") (pintype "input"))
    )
    (net (code "58") (name "PB6") (class "Default")
      (node (ref "U1") (pin "7") (pinfunction "(MISO)PB6_7") (pintype "bidirectional"))
    )
    (net (code "59") (name "PB7") (class "Default")
      (node (ref "U1") (pin "8") (pinfunction "(SCK)PB7_8") (pintype "bidirectional"))
      (node (ref "U8") (pin "2") (pinfunction "SCK_2") (pintype "input"))
    )
    (net (code "60") (name "PC0") (class "Default")
      (node (ref "IC2") (pin "12") (pinfunction "C_12") (pintype "input"))
      (node (ref "IC2") (pin "13") (pinfunction "C_13") (pintype "input"))
      (node (ref "IC2") (pin "5") (pinfunction "C_5") (pintype "input"))
      (node (ref "IC2") (pin "6") (pinfunction "C_6") (pintype "input"))
      (node (ref "U1") (pin "22") (pinfunction "(SCL)PC0_22") (pintype "bidirectional"))
    )
    (net (code "61") (name "PC1") (class "Default")
      (node (ref "U1") (pin "23") (pinfunction "(SDA)PC1_23") (pintype "bidirectional"))
      (node (ref "X1") (pin "5") (pinfunction "RW_5") (pintype "input"))
    )
    (net (code "62") (name "PC2") (class "Default")
      (node (ref "U1") (pin "24") (pinfunction "(TCK)PC2_24") (pintype "bidirectional"))
      (node (ref "X1") (pin "6") (pinfunction "E_6") (pintype "input"))
    )
    (net (code "63") (name "PC3") (class "Default")
      (node (ref "U1") (pin "25") (pinfunction "(TMS)PC3_25") (pintype "bidirectional"))
      (node (ref "X1") (pin "4") (pinfunction "RS_4") (pintype "input"))
    )
    (net (code "64") (name "PC4") (class "Default")
      (node (ref "IC2") (pin "10") (pinfunction "B_10") (pintype "tri_state"))
      (node (ref "U1") (pin "26") (pinfunction "(TDO)PC4_26") (pintype "bidirectional"))
      (node (ref "X1") (pin "11") (pinfunction "DB4_11") (pintype "bidirectional"))
    )
    (net (code "65") (name "PC5") (class "Default")
      (node (ref "IC2") (pin "9") (pinfunction "B_9") (pintype "tri_state"))
      (node (ref "U1") (pin "27") (pinfunction "(TDI)PC5_27") (pintype "bidirectional"))
      (node (ref "X1") (pin "12") (pinfunction "DB5_12") (pintype "bidirectional"))
    )
    (net (code "66") (name "PC6") (class "Default")
      (node (ref "IC2") (pin "3") (pinfunction "B_3") (pintype "tri_state"))
      (node (ref "U1") (pin "28") (pinfunction "(TOSC1)PC6_28") (pintype "bidirectional"))
      (node (ref "X1") (pin "13") (pinfunction "DB6_13") (pintype "bidirectional"))
    )
    (net (code "67") (name "PC7") (class "Default")
      (node (ref "IC2") (pin "2") (pinfunction "B_2") (pintype "tri_state"))
      (node (ref "U1") (pin "29") (pinfunction "(TOSC2)PC7_29") (pintype "bidirectional"))
      (node (ref "X1") (pin "14") (pinfunction "DB7_14") (pintype "bidirectional"))
    )
    (net (code "68") (name "PD0") (class "Default")
      (node (ref "U1") (pin "14") (pinfunction "(RXD)PD0_14") (pintype "bidirectional"))
    )
    (net (code "69") (name "PD1") (class "Default")
      (node (ref "U1") (pin "15") (pinfunction "(TXD)PD1_15") (pintype "bidirectional"))
    )
    (net (code "70") (name "PD2") (class "Default")
      (node (ref "U1") (pin "16") (pinfunction "(INT0)PD2_16") (pintype "bidirectional"))
    )
    (net (code "71") (name "PD3") (class "Default")
      (node (ref "U1") (pin "17") (pinfunction "(INT1)PD3_17") (pintype "bidirectional"))
    )
    (net (code "72") (name "PD4") (class "Default")
      (node (ref "U1") (pin "18") (pinfunction "(OC1B)PD4_18") (pintype "bidirectional"))
      (node (ref "U8") (pin "1") (pinfunction "~{CS/LD}_1") (pintype "input"))
    )
    (net (code "73") (name "PD7") (class "Default")
      (node (ref "U1") (pin "21") (pinfunction "(OC2)PD7_21") (pintype "bidirectional"))
    )
    (net (code "74") (name "VCC") (class "Default")
      (node (ref "C1") (pin "1") (pinfunction "+_1") (pintype "passive"))
      (node (ref "C2") (pin "2") (pinfunction "2_2") (pintype "passive"))
      (node (ref "C3") (pin "2") (pinfunction "2_2") (pintype "passive"))
      (node (ref "C4") (pin "1") (pinfunction "+_1") (pintype "passive"))
      (node (ref "IC3") (pin "8") (pinfunction "V+_8") (pintype "power_in"))
      (node (ref "IC4") (pin "3") (pinfunction "VO_3") (pintype "passive"))
      (node (ref "IC6") (pin "3") (pinfunction "VO_3") (pintype "passive"))
      (node (ref "Q3") (pin "3") (pinfunction "S_3") (pintype "passive"))
      (node (ref "Q6") (pin "3") (pinfunction "S_3") (pintype "passive"))
      (node (ref "R18") (pin "2") (pinfunction "2_2") (pintype "passive"))
      (node (ref "R19") (pin "2") (pinfunction "2_2") (pintype "passive"))
      (node (ref "R8") (pin "2") (pinfunction "2_2") (pintype "passive"))
      (node (ref "R9") (pin "2") (pinfunction "2_2") (pintype "passive"))
      (node (ref "U8") (pin "4") (pinfunction "REF_4") (pintype "input"))
      (node (ref "U8") (pin "6") (pinfunction "VCC_6") (pintype "power_in"))
    )
    (net (code "75") (name "VDD") (class "Default")
      (node (ref "X1") (pin "2") (pinfunction "VDD_2") (pintype "power_in"))
    )
    (net (code "76") (name "VSS") (class "Default")
      (node (ref "X1") (pin "1") (pinfunction "VSS_1") (pintype "power_in"))
    )
    (net (code "77") (name "unconnected-(J2-Pad1)") (class "Default")
      (node (ref "J2") (pin "1") (pinfunction "1_1") (pintype "passive"))
    )
    (net (code "78") (name "unconnected-(J2-Pad2)") (class "Default")
      (node (ref "J2") (pin "2") (pinfunction "2_2") (pintype "passive"))
    )
    (net (code "79") (name "unconnected-(J2-Pad3)") (class "Default")
      (node (ref "J2") (pin "3") (pinfunction "3_3") (pintype "passive"))
    )
    (net (code "80") (name "unconnected-(J2-Pad4)") (class "Default")
      (node (ref "J2") (pin "4") (pinfunction "4_4") (pintype "passive"))
    )
    (net (code "81") (name "unconnected-(J2-Pad5)") (class "Default")
      (node (ref "J2") (pin "5") (pinfunction "5_5") (pintype "passive"))
    )
    (net (code "82") (name "unconnected-(J2-Pad6)") (class "Default")
      (node (ref "J2") (pin "6") (pinfunction "6_6") (pintype "passive"))
    )
    (net (code "83") (name "unconnected-(J2-Pad8)") (class "Default")
      (node (ref "J2") (pin "8") (pinfunction "8_8") (pintype "passive"))
    )
    (net (code "84") (name "unconnected-(J2-Pad10)") (class "Default")
      (node (ref "J2") (pin "10") (pinfunction "10_10") (pintype "passive"))
    )
    (net (code "85") (name "unconnected-(J2-Pad12)") (class "Default")
      (node (ref "J2") (pin "12") (pinfunction "12_12") (pintype "passive"))
    )
    (net (code "86") (name "unconnected-(J2-Pad14)") (class "Default")
      (node (ref "J2") (pin "14") (pinfunction "14_14") (pintype "passive"))
    )
    (net (code "87") (name "unconnected-(J2-Pad16)") (class "Default")
      (node (ref "J2") (pin "16") (pinfunction "16_16") (pintype "passive"))
    )
    (net (code "88") (name "unconnected-(Q1-D-Pad2)") (class "Default")
      (node (ref "Q1") (pin "2") (pinfunction "D_2") (pintype "passive"))
    )
    (net (code "89") (name "unconnected-(Q2-D-Pad2)") (class "Default")
      (node (ref "Q2") (pin "2") (pinfunction "D_2") (pintype "passive"))
    )
    (net (code "90") (name "unconnected-(Q3-D-Pad2)") (class "Default")
      (node (ref "Q3") (pin "2") (pinfunction "D_2") (pintype "passive"))
    )
    (net (code "91") (name "unconnected-(Q4-D-Pad2)") (class "Default")
      (node (ref "Q4") (pin "2") (pinfunction "D_2") (pintype "passive"))
    )
    (net (code "92") (name "unconnected-(Q5-D-Pad2)") (class "Default")
      (node (ref "Q5") (pin "2") (pinfunction "D_2") (pintype "passive"))
    )
    (net (code "93") (name "unconnected-(Q6-D-Pad2)") (class "Default")
      (node (ref "Q6") (pin "2") (pinfunction "D_2") (pintype "passive"))
    )
    (net (code "94") (name "unconnected-(U1-XTAL1-Pad13)") (class "Default")
      (node (ref "U1") (pin "13") (pinfunction "XTAL1_13") (pintype "bidirectional"))
    )
    (net (code "95") (name "unconnected-(U1-XTAL2-Pad12)") (class "Default")
      (node (ref "U1") (pin "12") (pinfunction "XTAL2_12") (pintype "bidirectional"))
    )
    (net (code "96") (name "unconnected-(X1-A-Pad15)") (class "Default")
      (node (ref "X1") (pin "15") (pinfunction "A_15") (pintype "input"))
    )
    (net (code "97") (name "unconnected-(X1-DB0-Pad7)") (class "Default")
      (node (ref "X1") (pin "7") (pinfunction "DB0_7") (pintype "bidirectional"))
    )
    (net (code "98") (name "unconnected-(X1-DB1-Pad8)") (class "Default")
      (node (ref "X1") (pin "8") (pinfunction "DB1_8") (pintype "bidirectional"))
    )
    (net (code "99") (name "unconnected-(X1-DB2-Pad9)") (class "Default")
      (node (ref "X1") (pin "9") (pinfunction "DB2_9") (pintype "bidirectional"))
    )
    (net (code "100") (name "unconnected-(X1-DB3-Pad10)") (class "Default")
      (node (ref "X1") (pin "10") (pinfunction "DB3_10") (pintype "bidirectional"))
    )
    (net (code "101") (name "unconnected-(X1-K-Pad16)") (class "Default")
      (node (ref "X1") (pin "16") (pinfunction "K_16") (pintype "input"))
    )
    (net (code "102") (name "unconnected-(X1-VO-Pad3)") (class "Default")
      (node (ref "X1") (pin "3") (pinfunction "VO_3") (pintype "input"))
    )
  )
)
